# detector02.net
KiCad netlist of a schematic drawn in EAGLE
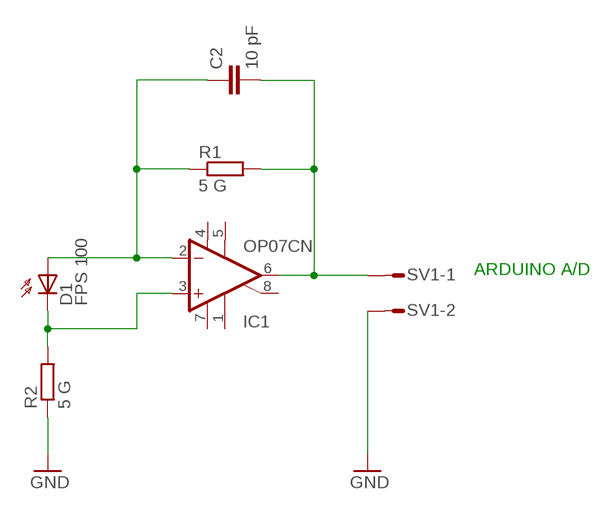
[diagram p0: schematic, sheet 1]

(export (version "E")
  (design (tool "Eeschema 10.0.6"))
  (components
    (comp (ref "C2")
      (value "10 pF")
      (footprint "eagle-import:C050-025X075")
      (libsource (lib "eagle-import") (part "C-EU050-025X075"))
    )
    (comp (ref "D1")
      (value "FPS 100")
      (footprint "eagle-import:BP104")
      (fields (field (name "MF") "VISHAY/TELEFUNKEN") (field (name "MPN") "BP104"))
      (libsource (lib "eagle-import") (part "BP104"))
    )
    (comp (ref "IC1")
      (value "OP07CN")
      (footprint "eagle-import:DIL08")
      (libsource (lib "eagle-import") (part "OP07NC"))
    )
    (comp (ref "R1")
      (value "5 G")
      (footprint "eagle-import:0207_7")
      (libsource (lib "eagle-import") (part "R-EU_0207/7"))
    )
    (comp (ref "R2")
      (value "5 G")
      (footprint "eagle-import:0207_7")
      (libsource (lib "eagle-import") (part "R-EU_0207/7"))
    )
    (comp (ref "SV1")
      (value "L02P")
      (footprint "eagle-import:L02P")
      (libsource (lib "eagle-import") (part "L02P"))
    )
  )
  (nets
    (net (code "1") (name "/V+") (class "Default")
      (node (ref "IC1") (pin "7") (pinfunction "V+_7") (pintype "power_in"))
    )
    (net (code "2") (name "/V-") (class "Default")
      (node (ref "IC1") (pin "4") (pinfunction "V-_4") (pintype "power_in"))
    )
    (net (code "3") (name "GND") (class "Default")
      (node (ref "R2") (pin "1") (pinfunction "1_1") (pintype "passive"))
      (node (ref "SV1") (pin "2") (pinfunction "S_2") (pintype "passive"))
    )
    (net (code "4") (name "Net-(D1-C)") (class "Default")
      (node (ref "D1") (pin "K") (pinfunction "C_K") (pintype "passive"))
      (node (ref "IC1") (pin "3") (pinfunction "+IN_3") (pintype "input"))
      (node (ref "R2") (pin "2") (pinfunction "2_2") (pintype "passive"))
    )
    (net (code "5") (name "Net-(IC1--IN)") (class "Default")
      (node (ref "C2") (pin "1") (pinfunction "1_1") (pintype "passive"))
      (node (ref "D1") (pin "A") (pinfunction "A_A") (pintype "passive"))
      (node (ref "IC1") (pin "2") (pinfunction "-IN_2") (pintype "input"))
      (node (ref "R1") (pin "1") (pinfunction "1_1") (pintype "passive"))
    )
    (net (code "6") (name "Net-(IC1-OUT)") (class "Default")
      (node (ref "C2") (pin "2") (pinfunction "2_2") (pintype "passive"))
      (node (ref "IC1") (pin "6") (pinfunction "OUT_6") (pintype "output"))
      (node (ref "R1") (pin "2") (pinfunction "2_2") (pintype "passive"))
      (node (ref "SV1") (pin "1") (pinfunction "S_1") (pintype "passive"))
    )
    (net (code "7") (name "unconnected-(IC1-ON1-Pad1)") (class "Default")
      (node (ref "IC1") (pin "1") (pinfunction "ON1_1") (pintype "passive"))
    )
    (net (code "8") (name "unconnected-(IC1-ON2-Pad8)") (class "Default")
      (node (ref "IC1") (pin "8") (pinfunction "ON2_8") (pintype "passive"))
    )
    (net (code "9") (name "unconnected-(IC1-OPT-Pad5)") (class "Default")
      (node (ref "IC1") (pin "5") (pinfunction "OPT_5") (pintype "passive"))
    )
  )
)
